# Crowtail-_A6_GPRS_GSM_Module_v1_0.net
KiCad netlist of a schematic drawn in EAGLE
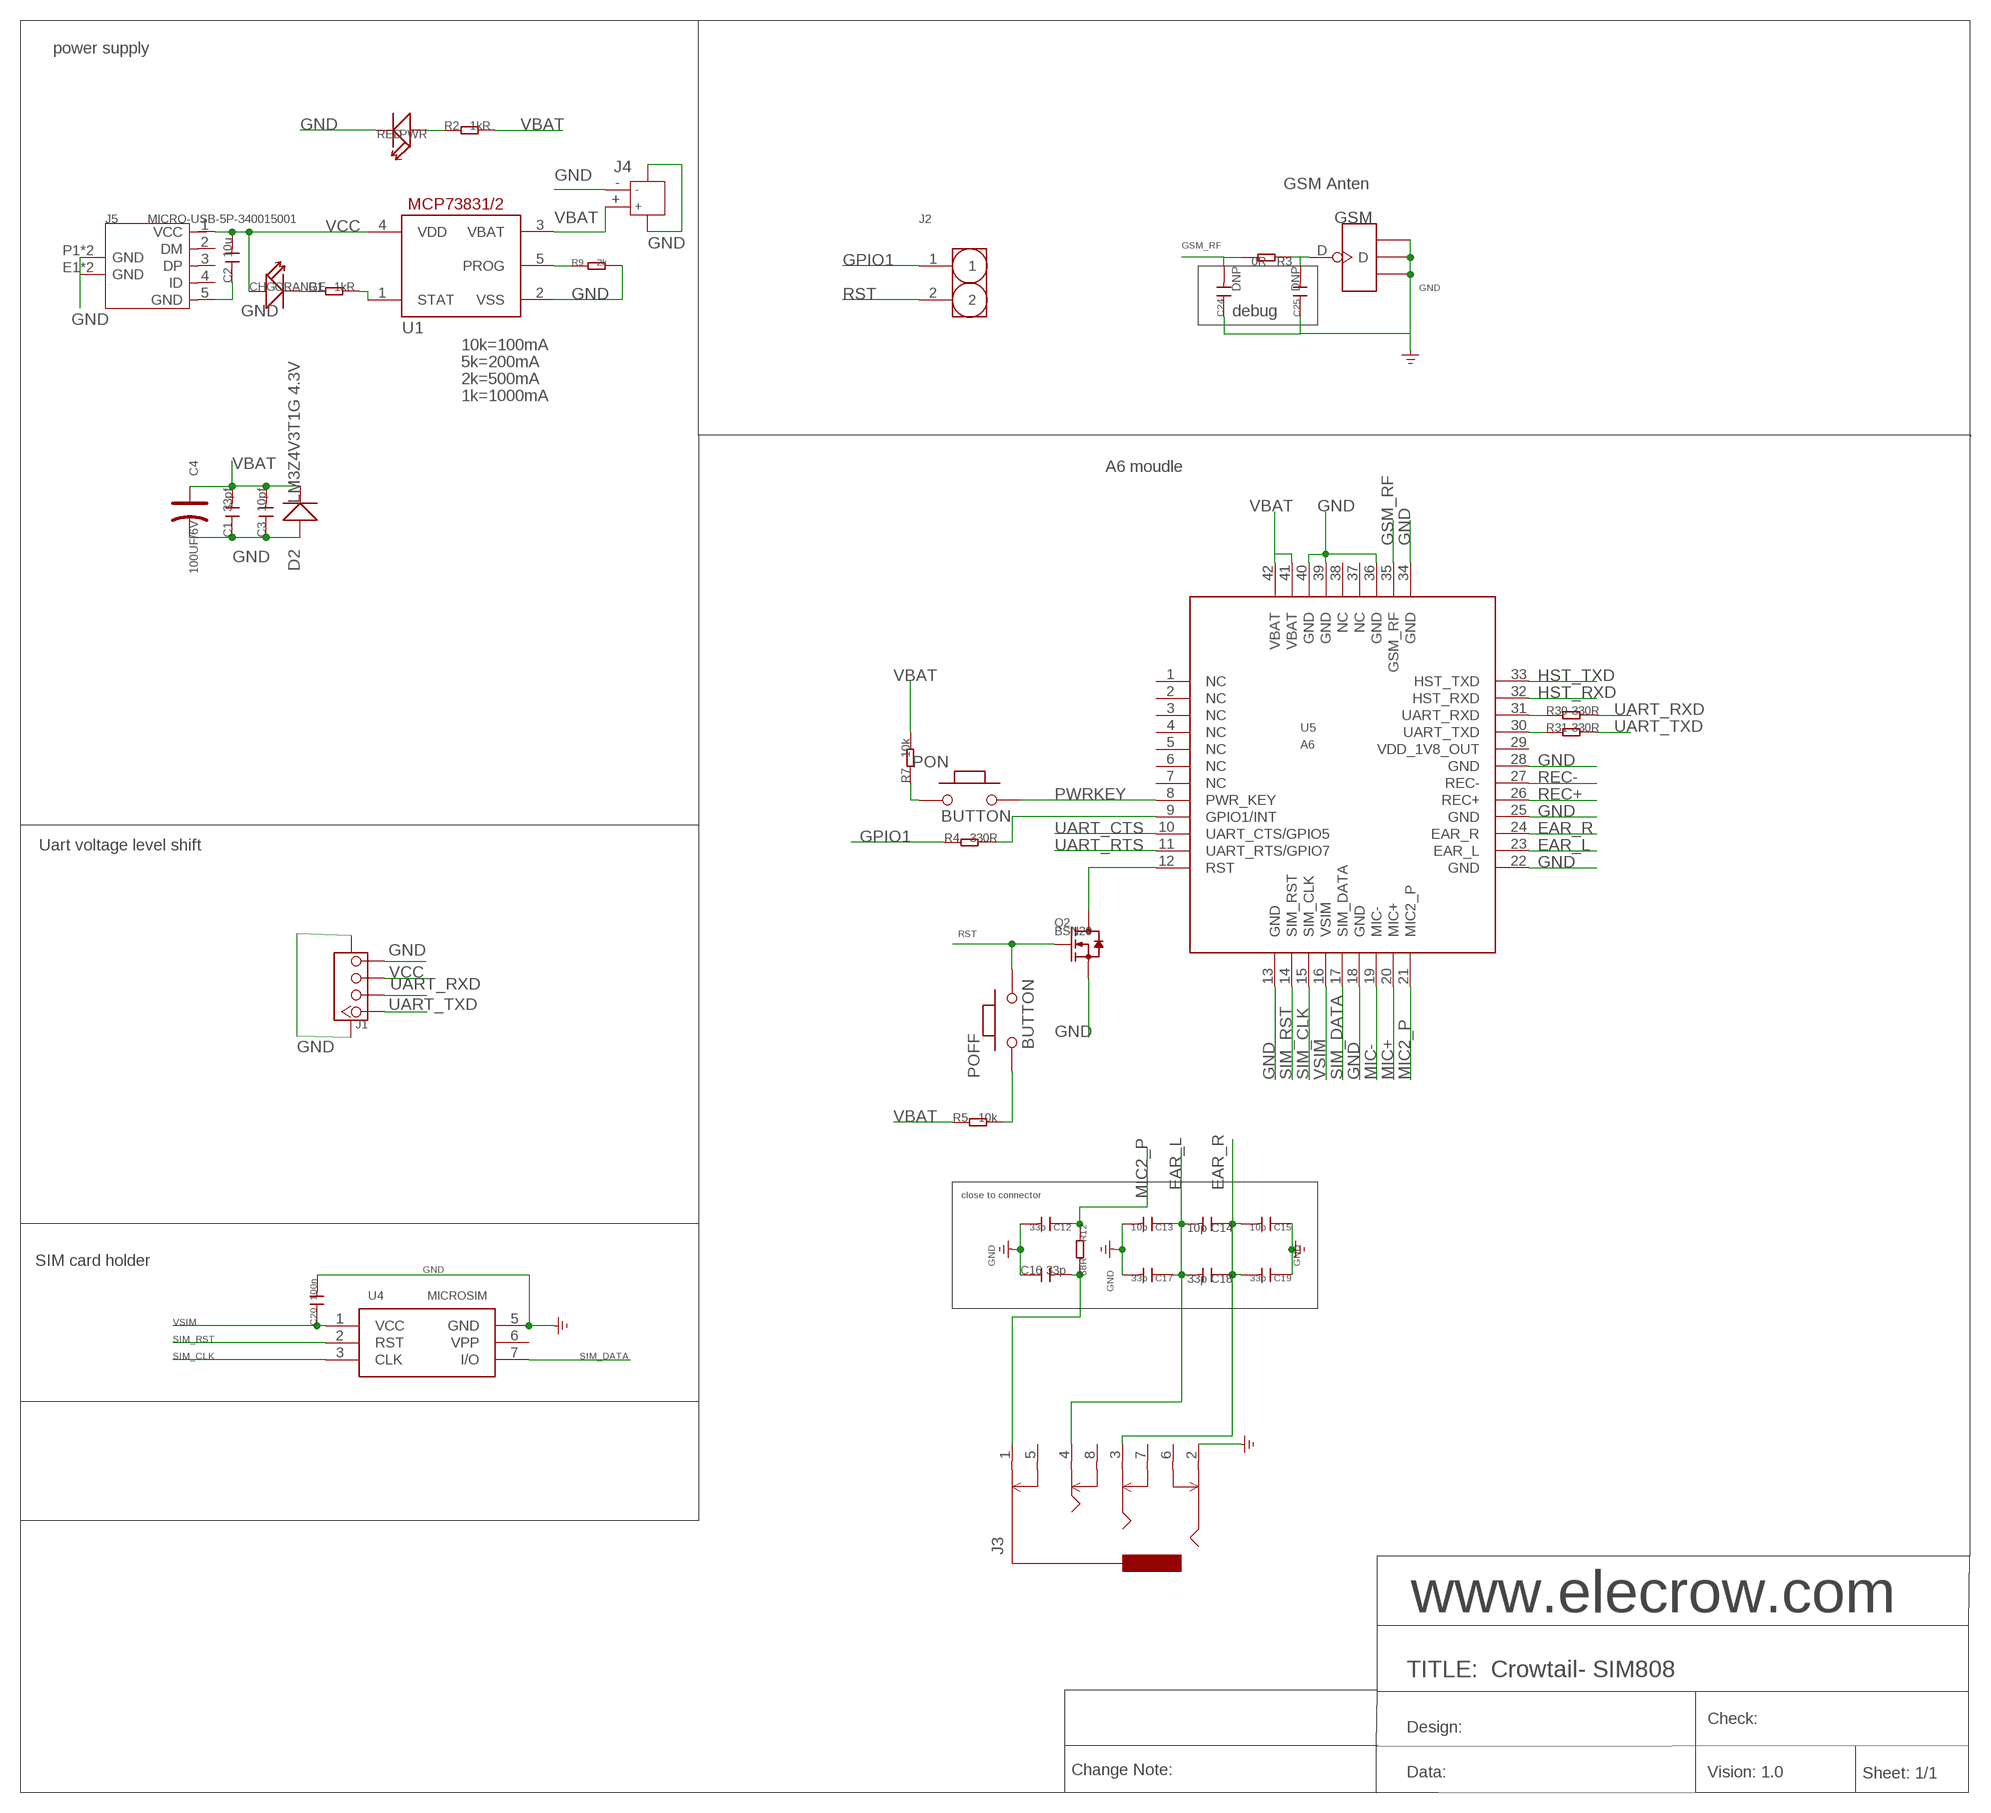
[diagram p0: schematic, sheet 1]

(export (version "E")
  (design (tool "Eeschema 10.0.6"))
  (components
    (comp (ref "C1")
      (value "33pf")
      (footprint "eagle-import:C0603")
      (libsource (lib "eagle-import") (part "C-0603"))
    )
    (comp (ref "C2")
      (value "10u")
      (footprint "eagle-import:C0603")
      (libsource (lib "eagle-import") (part "C-0603"))
    )
    (comp (ref "C3")
      (value "10pf")
      (footprint "eagle-import:C0603")
      (libsource (lib "eagle-import") (part "C-0603"))
    )
    (comp (ref "C4")
      (value "100UF/6V")
      (footprint "eagle-import:AVX-A")
      (libsource (lib "eagle-import") (part "CAP-AVX-A"))
    )
    (comp (ref "C12")
      (value "33p")
      (footprint "eagle-import:C0603")
      (libsource (lib "eagle-import") (part "C-0603"))
    )
    (comp (ref "C13")
      (value "10p")
      (footprint "eagle-import:C0402")
      (libsource (lib "eagle-import") (part "C-0402"))
    )
    (comp (ref "C14")
      (value "10p")
      (footprint "eagle-import:C0402")
      (libsource (lib "eagle-import") (part "C-0402"))
    )
    (comp (ref "C15")
      (value "10p")
      (footprint "eagle-import:C0402")
      (libsource (lib "eagle-import") (part "C-0402"))
    )
    (comp (ref "C16")
      (value "33p")
      (footprint "eagle-import:C0603")
      (libsource (lib "eagle-import") (part "C-0603"))
    )
    (comp (ref "C17")
      (value "33p")
      (footprint "eagle-import:C0402")
      (libsource (lib "eagle-import") (part "C-0402"))
    )
    (comp (ref "C18")
      (value "33p")
      (footprint "eagle-import:C0402")
      (libsource (lib "eagle-import") (part "C-0402"))
    )
    (comp (ref "C19")
      (value "33p")
      (footprint "eagle-import:C0402")
      (libsource (lib "eagle-import") (part "C-0402"))
    )
    (comp (ref "C20")
      (value "100n")
      (footprint "eagle-import:C0603")
      (libsource (lib "eagle-import") (part "C-0603"))
    )
    (comp (ref "C24")
      (value "DNP")
      (footprint "eagle-import:C0402")
      (libsource (lib "eagle-import") (part "C-0402"))
    )
    (comp (ref "C25")
      (value "DNP")
      (footprint "eagle-import:C0402")
      (libsource (lib "eagle-import") (part "C-0402"))
    )
    (comp (ref "CHG")
      (value "ORANGE")
      (footprint "eagle-import:D0603")
      (libsource (lib "eagle-import") (part "007-LED0603"))
    )
    (comp (ref "D2")
      (value "LM3Z4V3T1G 4.3V")
      (footprint "eagle-import:SOD323")
      (libsource (lib "eagle-import") (part "D'0805'"))
    )
    (comp (ref "GSM")
      (value "ANTENNA-U-FL")
      (footprint "eagle-import:4P-U-FL")
      (libsource (lib "eagle-import") (part "ANTENNA-U-FL"))
    )
    (comp (ref "J1")
      (value "TWIG-4P-2.0-SMD-FEMALE-REINFORCE'90D'")
      (footprint "eagle-import:4P-SMD-2.0-90D")
      (libsource (lib "eagle-import") (part "TWIG-4P-2.0-SMD-FEMALE-REINFORCE'90D'"))
    )
    (comp (ref "J2")
      (value "HEADER-2P-65/35MIL")
      (footprint "eagle-import:2P-2.54-65_35MIL")
      (libsource (lib "eagle-import") (part "HEADER-2P-65/35MIL"))
    )
    (comp (ref "J3")
      (value "AUDIO-8P'PJ-3536-L6S'")
      (footprint "eagle-import:8P-3.5-SMD")
      (libsource (lib "eagle-import") (part "AUDIO-8P'PJ-3536-L6S'"))
    )
    (comp (ref "J4")
      (value "JACK-JST-2P-SMD-PW'2.0'")
      (footprint "eagle-import:JST-SMD-2.0-90D")
      (libsource (lib "eagle-import") (part "JACK-JST-2P-SMD-PW'2.0'"))
    )
    (comp (ref "J5")
      (value "MICRO-USB-5P-340015001")
      (footprint "eagle-import:B-SMD-5P")
      (libsource (lib "eagle-import") (part "MICRO-USB-5P-340015001"))
    )
    (comp (ref "POFF")
      (value "BUTTON")
      (footprint "eagle-import:157SW")
      (libsource (lib "eagle-import") (part "PB157"))
    )
    (comp (ref "PON")
      (value "BUTTON")
      (footprint "eagle-import:157SW")
      (libsource (lib "eagle-import") (part "PB157"))
    )
    (comp (ref "PWR")
      (value "RED")
      (footprint "eagle-import:D0603")
      (libsource (lib "eagle-import") (part "007-LED0603"))
    )
    (comp (ref "Q2")
      (value "BSN20")
      (footprint "eagle-import:SOT23")
      (libsource (lib "eagle-import") (part "MOSFET-N'SOT23'"))
    )
    (comp (ref "R1")
      (value "1kR")
      (footprint "eagle-import:R0603")
      (libsource (lib "eagle-import") (part "R-0603"))
    )
    (comp (ref "R2")
      (value "1kR")
      (footprint "eagle-import:R0603")
      (libsource (lib "eagle-import") (part "R-0603"))
    )
    (comp (ref "R3")
      (value "0R")
      (footprint "eagle-import:R0603")
      (libsource (lib "eagle-import") (part "R-0603"))
    )
    (comp (ref "R4")
      (value "330R")
      (footprint "eagle-import:R0603")
      (libsource (lib "eagle-import") (part "R-0603"))
    )
    (comp (ref "R5")
      (value "10k")
      (footprint "eagle-import:R0603")
      (libsource (lib "eagle-import") (part "R-0603"))
    )
    (comp (ref "R7")
      (value "10k")
      (footprint "eagle-import:R0603")
      (libsource (lib "eagle-import") (part "R-0603"))
    )
    (comp (ref "R9")
      (value "2k")
      (footprint "eagle-import:R0603")
      (libsource (lib "eagle-import") (part "R-0603"))
    )
    (comp (ref "R12")
      (value "68R")
      (footprint "eagle-import:R0603")
      (libsource (lib "eagle-import") (part "R-0603"))
    )
    (comp (ref "R30")
      (value "330R")
      (footprint "eagle-import:R0603")
      (libsource (lib "eagle-import") (part "R-0603"))
    )
    (comp (ref "R31")
      (value "330R")
      (footprint "eagle-import:R0603")
      (libsource (lib "eagle-import") (part "R-0603"))
    )
    (comp (ref "U1")
      (value "MCP73831/OT")
      (footprint "eagle-import:SOT23-5L")
      (libsource (lib "eagle-import") (part "MCP73831/OT"))
    )
    (comp (ref "U4")
      (value "MICROSIM")
      (footprint "eagle-import:MICROSIM")
      (libsource (lib "eagle-import") (part "MICROSIM"))
    )
    (comp (ref "U5") (value "A6") (footprint "eagle-import:A6") (libsource (lib "eagle-import") (part "A6")))
  )
  (nets
    (net (code "1") (name "/EAR_L") (class "Default")
      (node (ref "C13") (pin "1") (pinfunction "1_1") (pintype "passive"))
      (node (ref "C14") (pin "2") (pinfunction "2_2") (pintype "passive"))
      (node (ref "C17") (pin "1") (pinfunction "1_1") (pintype "passive"))
      (node (ref "C18") (pin "2") (pinfunction "2_2") (pintype "passive"))
      (node (ref "J3") (pin "4") (pinfunction "4_4") (pintype "bidirectional"))
      (node (ref "U5") (pin "23") (pinfunction "EAR_L_23") (pintype "bidirectional"))
    )
    (net (code "2") (name "/EAR_R") (class "Default")
      (node (ref "C14") (pin "1") (pinfunction "1_1") (pintype "passive"))
      (node (ref "C15") (pin "2") (pinfunction "2_2") (pintype "passive"))
      (node (ref "C18") (pin "1") (pinfunction "1_1") (pintype "passive"))
      (node (ref "C19") (pin "2") (pinfunction "2_2") (pintype "passive"))
      (node (ref "J3") (pin "3") (pinfunction "3_3") (pintype "bidirectional"))
      (node (ref "U5") (pin "24") (pinfunction "EAR_R_24") (pintype "bidirectional"))
    )
    (net (code "3") (name "/GPIO1") (class "Default")
      (node (ref "J2") (pin "1") (pinfunction "1_1") (pintype "bidirectional"))
      (node (ref "R4") (pin "1") (pinfunction "1_1") (pintype "passive"))
    )
    (net (code "4") (name "/GSM_RF") (class "Default")
      (node (ref "C24") (pin "2") (pinfunction "2_2") (pintype "passive"))
      (node (ref "R3") (pin "2") (pinfunction "2_2") (pintype "passive"))
      (node (ref "U5") (pin "35") (pinfunction "GSM_RF_35") (pintype "bidirectional"))
    )
    (net (code "5") (name "/HST_RXD") (class "Default")
      (node (ref "U5") (pin "32") (pinfunction "HST_RXD_32") (pintype "bidirectional"))
    )
    (net (code "6") (name "/HST_TXD") (class "Default")
      (node (ref "U5") (pin "33") (pinfunction "HST_TXD_33") (pintype "bidirectional"))
    )
    (net (code "7") (name "/MIC+") (class "Default")
      (node (ref "U5") (pin "20") (pinfunction "MIC+_20") (pintype "bidirectional"))
    )
    (net (code "8") (name "/MIC-") (class "Default")
      (node (ref "U5") (pin "19") (pinfunction "MIC-_19") (pintype "bidirectional"))
    )
    (net (code "9") (name "/MIC2_P") (class "Default")
      (node (ref "C12") (pin "1") (pinfunction "1_1") (pintype "passive"))
      (node (ref "R12") (pin "1") (pinfunction "1_1") (pintype "passive"))
      (node (ref "U5") (pin "21") (pinfunction "MIC2_P_21") (pintype "bidirectional"))
    )
    (net (code "10") (name "/PWRKEY") (class "Default")
      (node (ref "PON") (pin "2") (pinfunction "2_2") (pintype "passive"))
      (node (ref "U5") (pin "8") (pinfunction "PWR_KEY_8") (pintype "bidirectional"))
    )
    (net (code "11") (name "/REC+") (class "Default")
      (node (ref "U5") (pin "26") (pinfunction "REC+_26") (pintype "bidirectional"))
    )
    (net (code "12") (name "/REC-") (class "Default")
      (node (ref "U5") (pin "27") (pinfunction "REC-_27") (pintype "bidirectional"))
    )
    (net (code "13") (name "/RST") (class "Default")
      (node (ref "J2") (pin "2") (pinfunction "2_2") (pintype "bidirectional"))
      (node (ref "POFF") (pin "2") (pinfunction "2_2") (pintype "passive"))
      (node (ref "Q2") (pin "1") (pinfunction "G_1") (pintype "passive"))
    )
    (net (code "14") (name "/SIM_CLK") (class "Default")
      (node (ref "U4") (pin "3") (pinfunction "CLK_3") (pintype "bidirectional"))
      (node (ref "U5") (pin "15") (pinfunction "SIM_CLK_15") (pintype "bidirectional"))
    )
    (net (code "15") (name "/SIM_DATA") (class "Default")
      (node (ref "U4") (pin "7") (pinfunction "I/O_7") (pintype "bidirectional"))
      (node (ref "U5") (pin "17") (pinfunction "SIM_DATA_17") (pintype "bidirectional"))
    )
    (net (code "16") (name "/SIM_RST") (class "Default")
      (node (ref "U4") (pin "2") (pinfunction "RST_2") (pintype "bidirectional"))
      (node (ref "U5") (pin "14") (pinfunction "SIM_RST_14") (pintype "bidirectional"))
    )
    (net (code "17") (name "/UART_CTS") (class "Default")
      (node (ref "U5") (pin "10") (pinfunction "UART_CTS/GPIO5_10") (pintype "bidirectional"))
    )
    (net (code "18") (name "/UART_RTS") (class "Default")
      (node (ref "U5") (pin "11") (pinfunction "UART_RTS/GPIO7_11") (pintype "bidirectional"))
    )
    (net (code "19") (name "/UART_RXD") (class "Default")
      (node (ref "J1") (pin "2") (pinfunction "2_2") (pintype "bidirectional"))
      (node (ref "R30") (pin "2") (pinfunction "2_2") (pintype "passive"))
    )
    (net (code "20") (name "/UART_TXD") (class "Default")
      (node (ref "J1") (pin "1") (pinfunction "1_1") (pintype "bidirectional"))
      (node (ref "R31") (pin "2") (pinfunction "2_2") (pintype "passive"))
    )
    (net (code "21") (name "/VBAT") (class "Default")
      (node (ref "C1") (pin "2") (pinfunction "2_2") (pintype "passive"))
      (node (ref "C3") (pin "2") (pinfunction "2_2") (pintype "passive"))
      (node (ref "C4") (pin "+") (pinfunction "+_+") (pintype "passive"))
      (node (ref "D2") (pin "-") (pinfunction "-_-") (pintype "passive"))
      (node (ref "J4") (pin "+") (pinfunction "1_+") (pintype "bidirectional"))
      (node (ref "R2") (pin "2") (pinfunction "2_2") (pintype "passive"))
      (node (ref "R5") (pin "1") (pinfunction "1_1") (pintype "passive"))
      (node (ref "R7") (pin "2") (pinfunction "2_2") (pintype "passive"))
      (node (ref "U1") (pin "3") (pinfunction "VBAT_3") (pintype "bidirectional"))
      (node (ref "U5") (pin "41") (pinfunction "VBAT_41") (pintype "bidirectional"))
      (node (ref "U5") (pin "42") (pinfunction "VBAT_42") (pintype "bidirectional"))
    )
    (net (code "22") (name "/VCC") (class "Default")
      (node (ref "C2") (pin "2") (pinfunction "2_2") (pintype "passive"))
      (node (ref "CHG") (pin "+") (pinfunction "+_+") (pintype "passive"))
      (node (ref "J1") (pin "3") (pinfunction "3_3") (pintype "bidirectional"))
      (node (ref "J5") (pin "1") (pinfunction "VCC_1") (pintype "bidirectional"))
      (node (ref "U1") (pin "4") (pinfunction "VDD_4") (pintype "power_in"))
    )
    (net (code "23") (name "/VSIM") (class "Default")
      (node (ref "C20") (pin "1") (pinfunction "1_1") (pintype "passive"))
      (node (ref "U4") (pin "1") (pinfunction "VCC_1") (pintype "bidirectional"))
      (node (ref "U5") (pin "16") (pinfunction "VSIM_16") (pintype "bidirectional"))
    )
    (net (code "24") (name "GND_POWER") (class "Default")
      (node (ref "C1") (pin "1") (pinfunction "1_1") (pintype "passive"))
      (node (ref "C12") (pin "2") (pinfunction "2_2") (pintype "passive"))
      (node (ref "C13") (pin "2") (pinfunction "2_2") (pintype "passive"))
      (node (ref "C15") (pin "1") (pinfunction "1_1") (pintype "passive"))
      (node (ref "C16") (pin "1") (pinfunction "1_1") (pintype "passive"))
      (node (ref "C17") (pin "2") (pinfunction "2_2") (pintype "passive"))
      (node (ref "C19") (pin "1") (pinfunction "1_1") (pintype "passive"))
      (node (ref "C2") (pin "1") (pinfunction "1_1") (pintype "passive"))
      (node (ref "C20") (pin "2") (pinfunction "2_2") (pintype "passive"))
      (node (ref "C24") (pin "1") (pinfunction "1_1") (pintype "passive"))
      (node (ref "C25") (pin "1") (pinfunction "1_1") (pintype "passive"))
      (node (ref "C3") (pin "1") (pinfunction "1_1") (pintype "passive"))
      (node (ref "C4") (pin "-") (pinfunction "-_-") (pintype "passive"))
      (node (ref "D2") (pin "+") (pinfunction "+_+") (pintype "passive"))
      (node (ref "GSM") (pin "GND1") (pinfunction "GND1_GND1") (pintype "bidirectional"))
      (node (ref "GSM") (pin "GND2") (pinfunction "GND2_GND2") (pintype "bidirectional"))
      (node (ref "GSM") (pin "GND3") (pinfunction "GND3_GND3") (pintype "bidirectional"))
      (node (ref "J1") (pin "4") (pinfunction "4_4") (pintype "bidirectional"))
      (node (ref "J1") (pin "SS1") (pinfunction "SS1_SS1") (pintype "bidirectional"))
      (node (ref "J1") (pin "SS2") (pinfunction "SS2_SS2") (pintype "bidirectional"))
      (node (ref "J3") (pin "2") (pinfunction "2_2") (pintype "bidirectional"))
      (node (ref "J4") (pin "-") (pinfunction "2_-") (pintype "bidirectional"))
      (node (ref "J4") (pin "3") (pinfunction "3_3") (pintype "bidirectional"))
      (node (ref "J4") (pin "4") (pinfunction "4_4") (pintype "bidirectional"))
      (node (ref "J5") (pin "5") (pinfunction "GND_5") (pintype "bidirectional"))
      (node (ref "J5") (pin "E1") (pinfunction "GND_E1") (pintype "bidirectional"))
      (node (ref "J5") (pin "E2") (pinfunction "GND_E2") (pintype "bidirectional"))
      (node (ref "J5") (pin "P1") (pinfunction "GND_P1") (pintype "bidirectional"))
      (node (ref "J5") (pin "P2") (pinfunction "GND_P2") (pintype "bidirectional"))
      (node (ref "PWR") (pin "-") (pinfunction "-_-") (pintype "passive"))
      (node (ref "Q2") (pin "2") (pinfunction "S_2") (pintype "passive"))
      (node (ref "R9") (pin "2") (pinfunction "2_2") (pintype "passive"))
      (node (ref "U1") (pin "2") (pinfunction "VSS_2") (pintype "power_in"))
      (node (ref "U4") (pin "5") (pinfunction "GND_5") (pintype "bidirectional"))
      (node (ref "U5") (pin "13") (pinfunction "GND_13") (pintype "bidirectional"))
      (node (ref "U5") (pin "18") (pinfunction "GND_18") (pintype "bidirectional"))
      (node (ref "U5") (pin "22") (pinfunction "GND_22") (pintype "bidirectional"))
      (node (ref "U5") (pin "25") (pinfunction "GND_25") (pintype "bidirectional"))
      (node (ref "U5") (pin "28") (pinfunction "GND_28") (pintype "bidirectional"))
      (node (ref "U5") (pin "34") (pinfunction "GND_34") (pintype "bidirectional"))
      (node (ref "U5") (pin "36") (pinfunction "GND_36") (pintype "bidirectional"))
      (node (ref "U5") (pin "39") (pinfunction "GND_39") (pintype "bidirectional"))
      (node (ref "U5") (pin "40") (pinfunction "GND_40") (pintype "bidirectional"))
    )
    (net (code "25") (name "Net-(C16-Pad2)") (class "Default")
      (node (ref "C16") (pin "2") (pinfunction "2_2") (pintype "passive"))
      (node (ref "J3") (pin "1") (pinfunction "1_1") (pintype "bidirectional"))
      (node (ref "R12") (pin "2") (pinfunction "2_2") (pintype "passive"))
    )
    (net (code "26") (name "Net-(C25-Pad2)") (class "Default")
      (node (ref "C25") (pin "2") (pinfunction "2_2") (pintype "passive"))
      (node (ref "GSM") (pin "D") (pinfunction "D_D") (pintype "bidirectional"))
      (node (ref "R3") (pin "1") (pinfunction "1_1") (pintype "passive"))
    )
    (net (code "27") (name "Net-(CHG-Pad-)") (class "Default")
      (node (ref "CHG") (pin "-") (pinfunction "-_-") (pintype "passive"))
      (node (ref "R1") (pin "1") (pinfunction "1_1") (pintype "passive"))
    )
    (net (code "28") (name "Net-(POFF-Pad1)") (class "Default")
      (node (ref "POFF") (pin "1") (pinfunction "1_1") (pintype "passive"))
      (node (ref "R5") (pin "2") (pinfunction "2_2") (pintype "passive"))
    )
    (net (code "29") (name "Net-(PON-Pad1)") (class "Default")
      (node (ref "PON") (pin "1") (pinfunction "1_1") (pintype "passive"))
      (node (ref "R7") (pin "1") (pinfunction "1_1") (pintype "passive"))
    )
    (net (code "30") (name "Net-(PWR-Pad+)") (class "Default")
      (node (ref "PWR") (pin "+") (pinfunction "+_+") (pintype "passive"))
      (node (ref "R2") (pin "1") (pinfunction "1_1") (pintype "passive"))
    )
    (net (code "31") (name "Net-(Q2-D)") (class "Default")
      (node (ref "Q2") (pin "3") (pinfunction "D_3") (pintype "passive"))
      (node (ref "U5") (pin "12") (pinfunction "RST_12") (pintype "bidirectional"))
    )
    (net (code "32") (name "Net-(U1-PROG)") (class "Default")
      (node (ref "R9") (pin "1") (pinfunction "1_1") (pintype "passive"))
      (node (ref "U1") (pin "5") (pinfunction "PROG_5") (pintype "input"))
    )
    (net (code "33") (name "Net-(U1-STAT)") (class "Default")
      (node (ref "R1") (pin "2") (pinfunction "2_2") (pintype "passive"))
      (node (ref "U1") (pin "1") (pinfunction "STAT_1") (pintype "output"))
    )
    (net (code "34") (name "Net-(U5-GPIO1{slash}INT)") (class "Default")
      (node (ref "R4") (pin "2") (pinfunction "2_2") (pintype "passive"))
      (node (ref "U5") (pin "9") (pinfunction "GPIO1/INT_9") (pintype "bidirectional"))
    )
    (net (code "35") (name "Net-(U5-UART_RXD)") (class "Default")
      (node (ref "R30") (pin "1") (pinfunction "1_1") (pintype "passive"))
      (node (ref "U5") (pin "31") (pinfunction "UART_RXD_31") (pintype "bidirectional"))
    )
    (net (code "36") (name "Net-(U5-UART_TXD)") (class "Default")
      (node (ref "R31") (pin "1") (pinfunction "1_1") (pintype "passive"))
      (node (ref "U5") (pin "30") (pinfunction "UART_TXD_30") (pintype "bidirectional"))
    )
    (net (code "37") (name "unconnected-(J3-Pad5)") (class "Default")
      (node (ref "J3") (pin "5") (pinfunction "5_5") (pintype "bidirectional"))
    )
    (net (code "38") (name "unconnected-(J3-Pad6)") (class "Default")
      (node (ref "J3") (pin "6") (pinfunction "6_6") (pintype "bidirectional"))
    )
    (net (code "39") (name "unconnected-(J3-Pad7)") (class "Default")
      (node (ref "J3") (pin "7") (pinfunction "7_7") (pintype "bidirectional"))
    )
    (net (code "40") (name "unconnected-(J3-Pad8)") (class "Default")
      (node (ref "J3") (pin "8") (pinfunction "8_8") (pintype "bidirectional"))
    )
    (net (code "41") (name "unconnected-(J5-DM-Pad2)") (class "Default")
      (node (ref "J5") (pin "2") (pinfunction "DM_2") (pintype "bidirectional"))
    )
    (net (code "42") (name "unconnected-(J5-DP-Pad3)") (class "Default")
      (node (ref "J5") (pin "3") (pinfunction "DP_3") (pintype "bidirectional"))
    )
    (net (code "43") (name "unconnected-(J5-ID-Pad4)") (class "Default")
      (node (ref "J5") (pin "4") (pinfunction "ID_4") (pintype "bidirectional"))
    )
    (net (code "44") (name "unconnected-(U4-VPP-Pad6)") (class "Default")
      (node (ref "U4") (pin "6") (pinfunction "VPP_6") (pintype "bidirectional"))
    )
    (net (code "45") (name "unconnected-(U5-NC-Pad1)") (class "Default")
      (node (ref "U5") (pin "1") (pinfunction "NC_1") (pintype "bidirectional"))
    )
    (net (code "46") (name "unconnected-(U5-NC-Pad2)") (class "Default")
      (node (ref "U5") (pin "2") (pinfunction "NC_2") (pintype "bidirectional"))
    )
    (net (code "47") (name "unconnected-(U5-NC-Pad3)") (class "Default")
      (node (ref "U5") (pin "3") (pinfunction "NC_3") (pintype "bidirectional"))
    )
    (net (code "48") (name "unconnected-(U5-NC-Pad4)") (class "Default")
      (node (ref "U5") (pin "4") (pinfunction "NC_4") (pintype "bidirectional"))
    )
    (net (code "49") (name "unconnected-(U5-NC-Pad5)") (class "Default")
      (node (ref "U5") (pin "5") (pinfunction "NC_5") (pintype "bidirectional"))
    )
    (net (code "50") (name "unconnected-(U5-NC-Pad6)") (class "Default")
      (node (ref "U5") (pin "6") (pinfunction "NC_6") (pintype "bidirectional"))
    )
    (net (code "51") (name "unconnected-(U5-NC-Pad7)") (class "Default")
      (node (ref "U5") (pin "7") (pinfunction "NC_7") (pintype "bidirectional"))
    )
    (net (code "52") (name "unconnected-(U5-NC-Pad37)") (class "Default")
      (node (ref "U5") (pin "37") (pinfunction "NC_37") (pintype "bidirectional"))
    )
    (net (code "53") (name "unconnected-(U5-NC-Pad38)") (class "Default")
      (node (ref "U5") (pin "38") (pinfunction "NC_38") (pintype "bidirectional"))
    )
    (net (code "54") (name "unconnected-(U5-VDD_1V8_OUT-Pad29)") (class "Default")
      (node (ref "U5") (pin "29") (pinfunction "VDD_1V8_OUT_29") (pintype "bidirectional"))
    )
  )
)
